# ESP8266_base5_1-2.net
KiCad netlist of a schematic drawn in Altium Designer
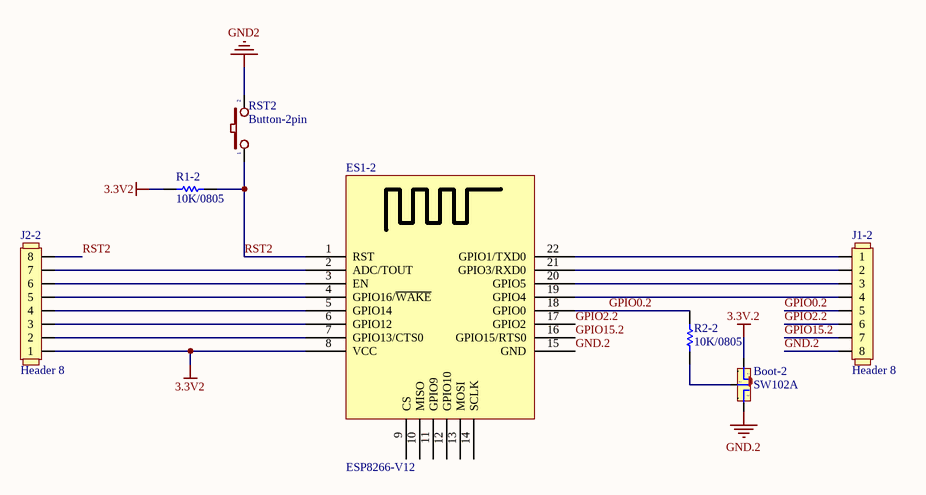
[diagram p0: ESP8266_base5.1-2.SchDoc]

(export (version "E")
  (design (tool "Eeschema 10.0.6"))
  (components
    (comp (ref "Boot-2")
      (value "SW102A")
      (footprint "SW102")
      (description "Switch 102 on Broad")
      (libsource (lib "syhaunguyen") (part "SW102A"))
    )
    (comp (ref "ES1-2")
      (value "ESP8266-V12")
      (footprint "ESP-8266 V12")
      (libsource (lib "Duc") (part "ESP8266-V12"))
    )
    (comp (ref "J1-2") (value "Header 8") (footprint "HEADER x8") (libsource (lib "Duc") (part "Header 8")))
    (comp (ref "J2-2") (value "Header 8") (footprint "HEADER x8") (libsource (lib "") (part "Header 8_1")))
    (comp (ref "R1-2")
      (value "10K/0805")
      (footprint "Res 0805(2012)")
      (description "Resistor 0805")
      (libsource (lib "Duc") (part "Resistor 0805"))
    )
    (comp (ref "R2-2")
      (value "10K/0805")
      (footprint "Res 0805(2012)")
      (description "Resistor 0805")
      (libsource (lib "Duc") (part "Resistor 0805"))
    )
    (comp (ref "RST2")
      (value "Button-2pin")
      (footprint "BUTTON_2P_SMD")
      (libsource (lib "Duc") (part "Button-2pin"))
    )
  )
  (nets
    (net (code "1") (name "/GPIO0.2") (class "Default")
      (node (ref "ES1-2") (pin "18") (pinfunction "GPIO0_18") (pintype "passive"))
      (node (ref "J1-2") (pin "5") (pinfunction "5_5") (pintype "passive"))
      (node (ref "R2-2") (pin "1") (pinfunction "1_1") (pintype "passive"))
    )
    (net (code "2") (name "/GPIO2.2") (class "Default")
      (node (ref "ES1-2") (pin "17") (pinfunction "GPIO2_17") (pintype "passive"))
      (node (ref "J1-2") (pin "6") (pinfunction "6_6") (pintype "passive"))
    )
    (net (code "3") (name "/GPIO15.2") (class "Default")
      (node (ref "ES1-2") (pin "16") (pinfunction "GPIO15/RTS0_16") (pintype "passive"))
      (node (ref "J1-2") (pin "7") (pinfunction "7_7") (pintype "passive"))
    )
    (net (code "4") (name "/RST2") (class "Default")
      (node (ref "ES1-2") (pin "1") (pinfunction "RST_1") (pintype "passive"))
      (node (ref "J2-2") (pin "8") (pinfunction "8_8") (pintype "passive"))
      (node (ref "R1-2") (pin "1") (pinfunction "1_1") (pintype "passive"))
      (node (ref "RST2") (pin "1") (pinfunction "1_1") (pintype "passive"))
    )
    (net (code "5") (name "3.3V.2") (class "Default")
      (node (ref "Boot-2") (pin "1") (pinfunction "1_1") (pintype "passive"))
    )
    (net (code "6") (name "3.3V2") (class "Default")
      (node (ref "ES1-2") (pin "8") (pinfunction "VCC_8") (pintype "passive"))
      (node (ref "J2-2") (pin "1") (pinfunction "1_1") (pintype "passive"))
      (node (ref "R1-2") (pin "2") (pinfunction "2_2") (pintype "passive"))
    )
    (net (code "7") (name "GND.2") (class "Default")
      (node (ref "Boot-2") (pin "3") (pinfunction "3_3") (pintype "passive"))
      (node (ref "ES1-2") (pin "15") (pinfunction "GND_15") (pintype "passive"))
      (node (ref "J1-2") (pin "8") (pinfunction "8_8") (pintype "passive"))
    )
    (net (code "8") (name "GND2") (class "Default")
      (node (ref "RST2") (pin "2") (pinfunction "2_2") (pintype "passive"))
    )
    (net (code "9") (name "Net-(Boot-2-Pad2)") (class "Default")
      (node (ref "Boot-2") (pin "2") (pinfunction "2_2") (pintype "passive"))
      (node (ref "R2-2") (pin "2") (pinfunction "2_2") (pintype "passive"))
    )
    (net (code "10") (name "Net-(ES1-2-ADC{slash}TOUT)") (class "Default")
      (node (ref "ES1-2") (pin "2") (pinfunction "ADC/TOUT_2") (pintype "passive"))
      (node (ref "J2-2") (pin "7") (pinfunction "7_7") (pintype "passive"))
    )
    (net (code "11") (name "Net-(ES1-2-EN)") (class "Default")
      (node (ref "ES1-2") (pin "3") (pinfunction "EN_3") (pintype "passive"))
      (node (ref "J2-2") (pin "6") (pinfunction "6_6") (pintype "passive"))
    )
    (net (code "12") (name "Net-(ES1-2-GPIO1{slash}TXD0)") (class "Default")
      (node (ref "ES1-2") (pin "22") (pinfunction "GPIO1/TXD0_22") (pintype "passive"))
      (node (ref "J1-2") (pin "1") (pinfunction "1_1") (pintype "passive"))
    )
    (net (code "13") (name "Net-(ES1-2-GPIO3{slash}RXD0)") (class "Default")
      (node (ref "ES1-2") (pin "21") (pinfunction "GPIO3/RXD0_21") (pintype "passive"))
      (node (ref "J1-2") (pin "2") (pinfunction "2_2") (pintype "passive"))
    )
    (net (code "14") (name "Net-(ES1-2-GPIO4)") (class "Default")
      (node (ref "ES1-2") (pin "19") (pinfunction "GPIO4_19") (pintype "passive"))
      (node (ref "J1-2") (pin "4") (pinfunction "4_4") (pintype "passive"))
    )
    (net (code "15") (name "Net-(ES1-2-GPIO5)") (class "Default")
      (node (ref "ES1-2") (pin "20") (pinfunction "GPIO5_20") (pintype "passive"))
      (node (ref "J1-2") (pin "3") (pinfunction "3_3") (pintype "passive"))
    )
    (net (code "16") (name "Net-(ES1-2-GPIO12)") (class "Default")
      (node (ref "ES1-2") (pin "6") (pinfunction "GPIO12_6") (pintype "passive"))
      (node (ref "J2-2") (pin "3") (pinfunction "3_3") (pintype "passive"))
    )
    (net (code "17") (name "Net-(ES1-2-GPIO13{slash}CTS0)") (class "Default")
      (node (ref "ES1-2") (pin "7") (pinfunction "GPIO13/CTS0_7") (pintype "passive"))
      (node (ref "J2-2") (pin "2") (pinfunction "2_2") (pintype "passive"))
    )
    (net (code "18") (name "Net-(ES1-2-GPIO14)") (class "Default")
      (node (ref "ES1-2") (pin "5") (pinfunction "GPIO14_5") (pintype "passive"))
      (node (ref "J2-2") (pin "4") (pinfunction "4_4") (pintype "passive"))
    )
    (net (code "19") (name "Net-(ES1-2-GPIO16{slash}~{WAKE})") (class "Default")
      (node (ref "ES1-2") (pin "4") (pinfunction "GPIO16/~{WAKE}_4") (pintype "passive"))
      (node (ref "J2-2") (pin "5") (pinfunction "5_5") (pintype "passive"))
    )
    (net (code "20") (name "unconnected-(Boot-2-Pad4)") (class "Default")
      (node (ref "Boot-2") (pin "4") (pinfunction "4_4") (pintype "passive"))
    )
    (net (code "21") (name "unconnected-(Boot-2-Pad5)") (class "Default")
      (node (ref "Boot-2") (pin "5") (pinfunction "5_5") (pintype "passive"))
    )
    (net (code "22") (name "unconnected-(ES1-2-CS-Pad9)") (class "Default")
      (node (ref "ES1-2") (pin "9") (pinfunction "CS_9") (pintype "passive"))
    )
    (net (code "23") (name "unconnected-(ES1-2-GPIO9-Pad11)") (class "Default")
      (node (ref "ES1-2") (pin "11") (pinfunction "GPIO9_11") (pintype "passive"))
    )
    (net (code "24") (name "unconnected-(ES1-2-GPIO10-Pad12)") (class "Default")
      (node (ref "ES1-2") (pin "12") (pinfunction "GPIO10_12") (pintype "passive"))
    )
    (net (code "25") (name "unconnected-(ES1-2-MISO-Pad10)") (class "Default")
      (node (ref "ES1-2") (pin "10") (pinfunction "MISO_10") (pintype "passive"))
    )
    (net (code "26") (name "unconnected-(ES1-2-MOSI-Pad13)") (class "Default")
      (node (ref "ES1-2") (pin "13") (pinfunction "MOSI_13") (pintype "passive"))
    )
    (net (code "27") (name "unconnected-(ES1-2-SCLK-Pad14)") (class "Default")
      (node (ref "ES1-2") (pin "14") (pinfunction "SCLK_14") (pintype "passive"))
    )
  )
)
